# Main_ATMEGA328P.net
KiCad netlist of a schematic drawn in EAGLE
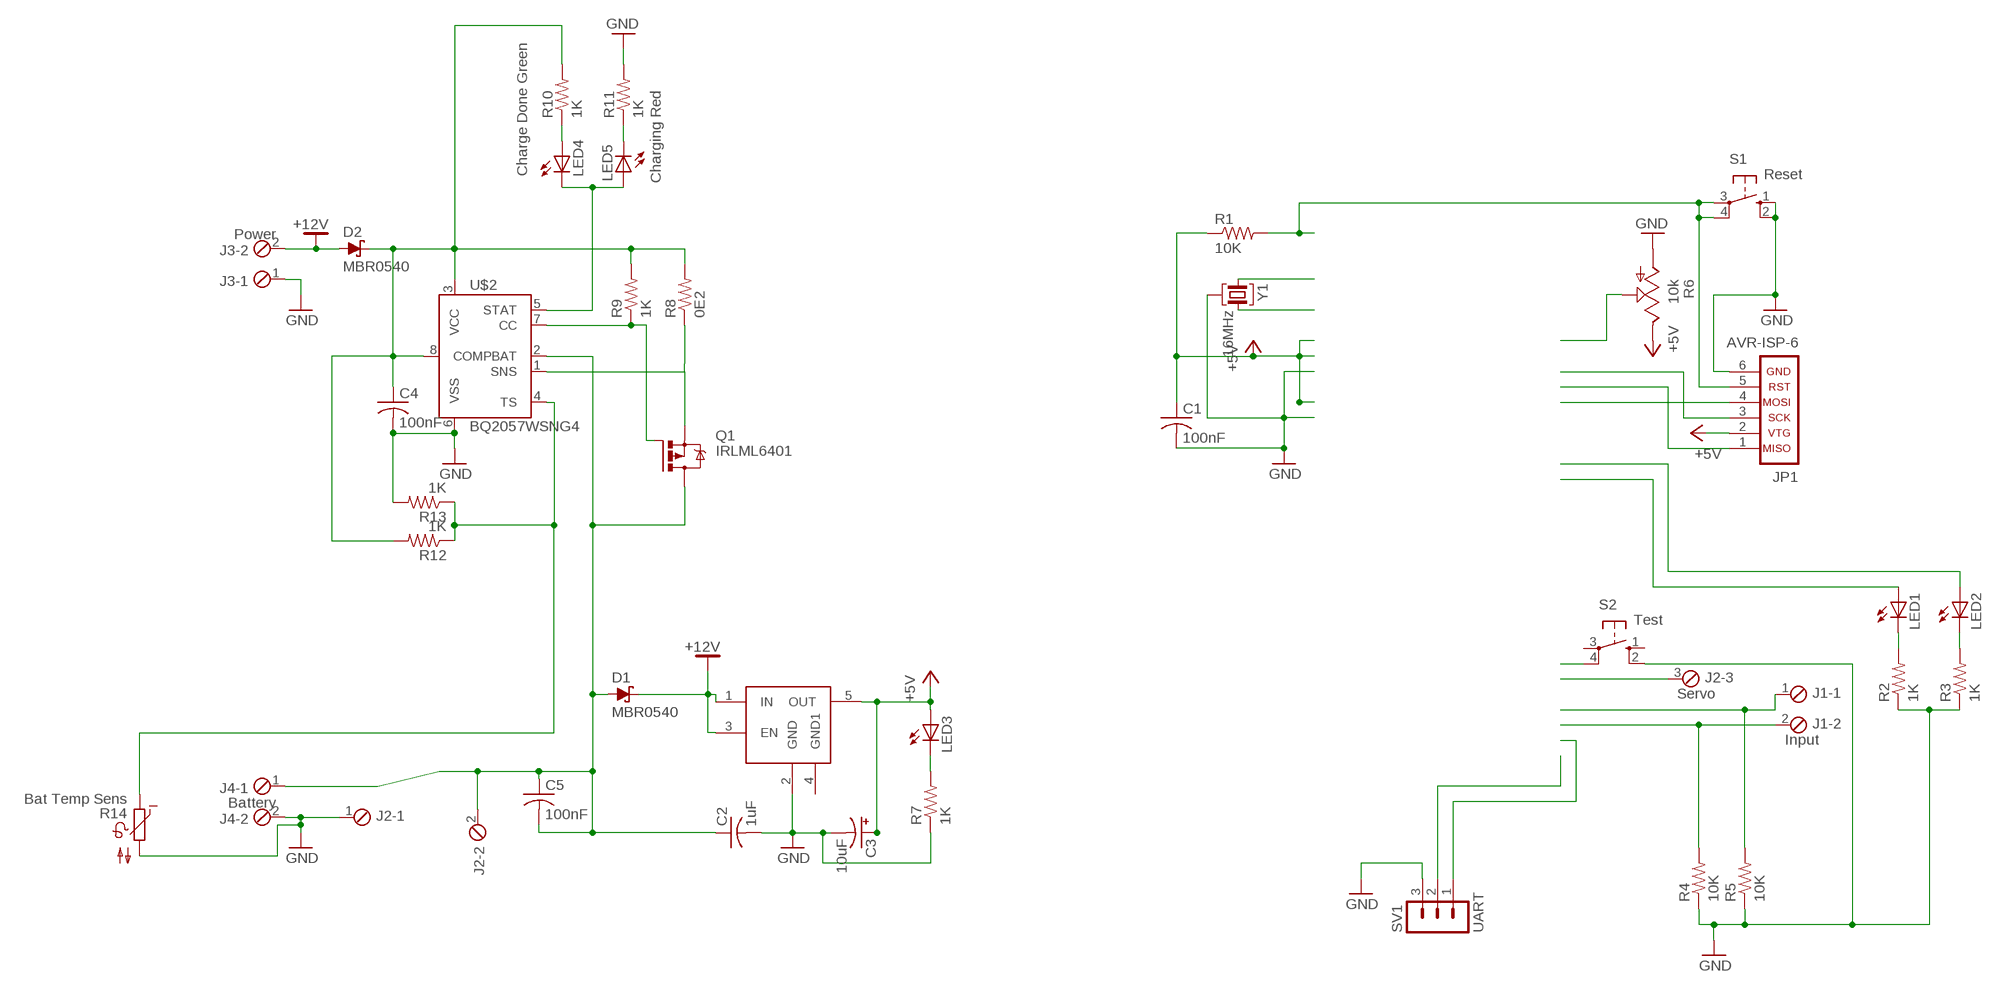
[diagram p0: schematic, sheet 1]

(export (version "E")
  (design (tool "Eeschema 10.0.6"))
  (components
    (comp (ref "C1")
      (value "100nF")
      (footprint "eagle-import:C0805K")
      (libsource (lib "eagle-import") (part "C-USC0805K"))
    )
    (comp (ref "C2")
      (value "1uF")
      (footprint "eagle-import:C0805K")
      (libsource (lib "eagle-import") (part "C-USC0805K"))
    )
    (comp (ref "C3")
      (value "10uF")
      (footprint "eagle-import:E2,5-7")
      (libsource (lib "eagle-import") (part "CPOL-USE2.5-7"))
    )
    (comp (ref "C4")
      (value "100nF")
      (footprint "eagle-import:C0805K")
      (libsource (lib "eagle-import") (part "C-USC0805K"))
    )
    (comp (ref "C5")
      (value "100nF")
      (footprint "eagle-import:C0805K")
      (libsource (lib "eagle-import") (part "C-USC0805K"))
    )
    (comp (ref "D1")
      (value "MBR0540")
      (footprint "eagle-import:SOD123")
      (libsource (lib "eagle-import") (part "MBR0540"))
    )
    (comp (ref "D2")
      (value "MBR0540")
      (footprint "eagle-import:SOD123")
      (libsource (lib "eagle-import") (part "MBR0540"))
    )
    (comp (ref "J1")
      (value "Input")
      (footprint "eagle-import:796689-2")
      (libsource (lib "eagle-import") (part "796689-2"))
    )
    (comp (ref "J2")
      (value "Servo")
      (footprint "eagle-import:796689-3")
      (libsource (lib "eagle-import") (part "796689-3"))
    )
    (comp (ref "J3")
      (value "Power")
      (footprint "eagle-import:796689-2")
      (libsource (lib "eagle-import") (part "796689-2"))
    )
    (comp (ref "J4")
      (value "Battery")
      (footprint "eagle-import:796689-2")
      (libsource (lib "eagle-import") (part "796689-2"))
    )
    (comp (ref "JP1")
      (value "AVR-ISP-6")
      (footprint "eagle-import:AVR-ISP-6")
      (libsource (lib "eagle-import") (part "AVR-ISP-6"))
    )
    (comp (ref "LED1")
      (value "LEDCHIPLED_0805")
      (footprint "eagle-import:CHIPLED_0805")
      (libsource (lib "eagle-import") (part "LEDCHIPLED_0805"))
    )
    (comp (ref "LED2")
      (value "LEDCHIPLED_0805")
      (footprint "eagle-import:CHIPLED_0805")
      (libsource (lib "eagle-import") (part "LEDCHIPLED_0805"))
    )
    (comp (ref "LED3")
      (value "LEDCHIPLED_0805")
      (footprint "eagle-import:CHIPLED_0805")
      (libsource (lib "eagle-import") (part "LEDCHIPLED_0805"))
    )
    (comp (ref "LED4")
      (value "Charge Done Green")
      (footprint "eagle-import:CHIPLED_0805")
      (libsource (lib "eagle-import") (part "LEDCHIPLED_0805"))
    )
    (comp (ref "LED5")
      (value "Charging Red")
      (footprint "eagle-import:CHIPLED_0805")
      (libsource (lib "eagle-import") (part "LEDCHIPLED_0805"))
    )
    (comp (ref "Q1")
      (value "IRLML6401")
      (footprint "eagle-import:MICRO3")
      (libsource (lib "eagle-import") (part "IRLML5203"))
    )
    (comp (ref "R1")
      (value "10K")
      (footprint "eagle-import:R0805")
      (libsource (lib "eagle-import") (part "R-US_R0805"))
    )
    (comp (ref "R2")
      (value "1K")
      (footprint "eagle-import:R0805")
      (libsource (lib "eagle-import") (part "R-US_R0805"))
    )
    (comp (ref "R3")
      (value "1K")
      (footprint "eagle-import:R0805")
      (libsource (lib "eagle-import") (part "R-US_R0805"))
    )
    (comp (ref "R4")
      (value "10K")
      (footprint "eagle-import:R0805")
      (libsource (lib "eagle-import") (part "R-US_R0805"))
    )
    (comp (ref "R5")
      (value "10K")
      (footprint "eagle-import:R0805")
      (libsource (lib "eagle-import") (part "R-US_R0805"))
    )
    (comp (ref "R6")
      (value "10k")
      (footprint "eagle-import:PT-10")
      (libsource (lib "eagle-import") (part "TRIM_US-PT-10"))
    )
    (comp (ref "R7")
      (value "1K")
      (footprint "eagle-import:R0805")
      (libsource (lib "eagle-import") (part "R-US_R0805"))
    )
    (comp (ref "R8")
      (value "0E2")
      (footprint "eagle-import:M1206")
      (libsource (lib "eagle-import") (part "R-US_M1206"))
    )
    (comp (ref "R9")
      (value "1K")
      (footprint "eagle-import:R0805")
      (libsource (lib "eagle-import") (part "R-US_R0805"))
    )
    (comp (ref "R10")
      (value "1K")
      (footprint "eagle-import:R0805")
      (libsource (lib "eagle-import") (part "R-US_R0805"))
    )
    (comp (ref "R11")
      (value "1K")
      (footprint "eagle-import:R0805")
      (libsource (lib "eagle-import") (part "R-US_R0805"))
    )
    (comp (ref "R12")
      (value "1K")
      (footprint "eagle-import:R0805")
      (libsource (lib "eagle-import") (part "R-US_R0805"))
    )
    (comp (ref "R13")
      (value "1K")
      (footprint "eagle-import:R0805")
      (libsource (lib "eagle-import") (part "R-US_R0805"))
    )
    (comp (ref "R14")
      (value "Bat Temp Sens")
      (footprint "eagle-import:P640")
      (libsource (lib "eagle-import") (part "NTC640"))
    )
    (comp (ref "S1")
      (value "Reset")
      (footprint "eagle-import:B3F-10XX")
      (fields (field (name "MPN") "B3F-1000"))
      (libsource (lib "eagle-import") (part "10-XX"))
    )
    (comp (ref "S2")
      (value "Test")
      (footprint "eagle-import:B3F-10XX")
      (fields (field (name "MPN") "B3F-1000"))
      (libsource (lib "eagle-import") (part "10-XX"))
    )
    (comp (ref "SV1")
      (value "UART")
      (footprint "eagle-import:MA03-1")
      (libsource (lib "eagle-import") (part "MA03-1"))
    )
    (comp (ref "U$1")
      (value "LP2981-50")
      (footprint "eagle-import:DBV-R-PDSO-G5")
      (libsource (lib "eagle-import") (part "TPS783XX"))
    )
    (comp (ref "U$2")
      (value "BQ2057WSNG4")
      (footprint "eagle-import:D_R-PDSO-G8")
      (libsource (lib "eagle-import") (part "BQ2057WSNG4"))
    )
    (comp (ref "Y1")
      (value "16MHz")
      (footprint "eagle-import:5X10-3")
      (libsource (lib "eagle-import") (part "ZTT5X10"))
    )
  )
  (nets
    (net (code "1") (name "+5V") (class "Default")
      (node (ref "C1") (pin "1") (pinfunction "1_1") (pintype "passive"))
      (node (ref "C3") (pin "+") (pinfunction "+_+") (pintype "passive"))
      (node (ref "JP1") (pin "2") (pinfunction "2_2") (pintype "passive"))
      (node (ref "LED3") (pin "A") (pinfunction "A_A") (pintype "passive"))
      (node (ref "R1") (pin "1") (pinfunction "1_1") (pintype "passive"))
      (node (ref "R6") (pin "E") (pinfunction "E_E") (pintype "passive"))
      (node (ref "U$1") (pin "5") (pinfunction "OUT_5") (pintype "bidirectional"))
    )
    (net (code "2") (name "+12V") (class "Default")
      (node (ref "D1") (pin "C") (pinfunction "C_C") (pintype "passive"))
      (node (ref "D2") (pin "A") (pinfunction "A_A") (pintype "passive"))
      (node (ref "J3") (pin "2") (pinfunction "1_2") (pintype "passive"))
      (node (ref "U$1") (pin "1") (pinfunction "IN_1") (pintype "bidirectional"))
      (node (ref "U$1") (pin "3") (pinfunction "EN_3") (pintype "bidirectional"))
    )
    (net (code "3") (name "GND") (class "Default")
      (node (ref "C1") (pin "2") (pinfunction "2_2") (pintype "passive"))
      (node (ref "C2") (pin "2") (pinfunction "2_2") (pintype "passive"))
      (node (ref "C3") (pin "-") (pinfunction "-_-") (pintype "passive"))
      (node (ref "C4") (pin "2") (pinfunction "2_2") (pintype "passive"))
      (node (ref "J2") (pin "1") (pinfunction "1_1") (pintype "passive"))
      (node (ref "J3") (pin "1") (pinfunction "1_1") (pintype "passive"))
      (node (ref "J4") (pin "2") (pinfunction "1_2") (pintype "passive"))
      (node (ref "JP1") (pin "6") (pinfunction "6_6") (pintype "passive"))
      (node (ref "R11") (pin "2") (pinfunction "2_2") (pintype "passive"))
      (node (ref "R13") (pin "2") (pinfunction "2_2") (pintype "passive"))
      (node (ref "R14") (pin "2") (pinfunction "2_2") (pintype "passive"))
      (node (ref "R2") (pin "1") (pinfunction "1_1") (pintype "passive"))
      (node (ref "R3") (pin "1") (pinfunction "1_1") (pintype "passive"))
      (node (ref "R4") (pin "1") (pinfunction "1_1") (pintype "passive"))
      (node (ref "R5") (pin "1") (pinfunction "1_1") (pintype "passive"))
      (node (ref "R6") (pin "A") (pinfunction "A_A") (pintype "passive"))
      (node (ref "R7") (pin "1") (pinfunction "1_1") (pintype "passive"))
      (node (ref "S1") (pin "1") (pinfunction "S_1") (pintype "passive"))
      (node (ref "S1") (pin "2") (pinfunction "S1_2") (pintype "passive"))
      (node (ref "S2") (pin "2") (pinfunction "S1_2") (pintype "passive"))
      (node (ref "SV1") (pin "3") (pinfunction "3_3") (pintype "passive"))
      (node (ref "U$1") (pin "2") (pinfunction "GND_2") (pintype "bidirectional"))
      (node (ref "U$2") (pin "6") (pinfunction "VSS_6") (pintype "power_in"))
      (node (ref "Y1") (pin "2") (pinfunction "2_2") (pintype "passive"))
    )
    (net (code "4") (name "Net-(J1-Pad1)") (class "Default")
      (node (ref "J1") (pin "1") (pinfunction "1_1") (pintype "passive"))
      (node (ref "R5") (pin "2") (pinfunction "2_2") (pintype "passive"))
    )
    (net (code "5") (name "Net-(J1B-1)") (class "Default")
      (node (ref "J1") (pin "2") (pinfunction "1_2") (pintype "passive"))
      (node (ref "R4") (pin "2") (pinfunction "2_2") (pintype "passive"))
    )
    (net (code "6") (name "Net-(J2B-1)") (class "Default")
      (node (ref "C2") (pin "1") (pinfunction "1_1") (pintype "passive"))
      (node (ref "C5") (pin "1") (pinfunction "1_1") (pintype "passive"))
      (node (ref "C5") (pin "2") (pinfunction "2_2") (pintype "passive"))
      (node (ref "D1") (pin "A") (pinfunction "A_A") (pintype "passive"))
      (node (ref "J2") (pin "2") (pinfunction "1_2") (pintype "passive"))
      (node (ref "J4") (pin "1") (pinfunction "1_1") (pintype "passive"))
      (node (ref "Q1") (pin "3") (pinfunction "D_3") (pintype "passive"))
      (node (ref "U$2") (pin "2") (pinfunction "BAT_2") (pintype "input"))
    )
    (net (code "7") (name "Net-(LED1-PadC)") (class "Default")
      (node (ref "LED1") (pin "C") (pinfunction "C_C") (pintype "passive"))
      (node (ref "R2") (pin "2") (pinfunction "2_2") (pintype "passive"))
    )
    (net (code "8") (name "Net-(LED2-PadC)") (class "Default")
      (node (ref "LED2") (pin "C") (pinfunction "C_C") (pintype "passive"))
      (node (ref "R3") (pin "2") (pinfunction "2_2") (pintype "passive"))
    )
    (net (code "9") (name "Net-(LED3-PadC)") (class "Default")
      (node (ref "LED3") (pin "C") (pinfunction "C_C") (pintype "passive"))
      (node (ref "R7") (pin "2") (pinfunction "2_2") (pintype "passive"))
    )
    (net (code "10") (name "Net-(LED4-PadA)") (class "Default")
      (node (ref "LED4") (pin "A") (pinfunction "A_A") (pintype "passive"))
      (node (ref "R10") (pin "1") (pinfunction "1_1") (pintype "passive"))
    )
    (net (code "11") (name "Net-(LED5-PadC)") (class "Default")
      (node (ref "LED5") (pin "C") (pinfunction "C_C") (pintype "passive"))
      (node (ref "R11") (pin "1") (pinfunction "1_1") (pintype "passive"))
    )
    (net (code "12") (name "Net-(Q1-G)") (class "Default")
      (node (ref "Q1") (pin "1") (pinfunction "G_1") (pintype "passive"))
      (node (ref "R9") (pin "1") (pinfunction "1_1") (pintype "passive"))
      (node (ref "U$2") (pin "7") (pinfunction "CC_7") (pintype "output"))
    )
    (net (code "13") (name "Net-(Q1-S)") (class "Default")
      (node (ref "Q1") (pin "2") (pinfunction "S_2") (pintype "passive"))
      (node (ref "R8") (pin "1") (pinfunction "1_1") (pintype "passive"))
      (node (ref "U$2") (pin "1") (pinfunction "SNS_1") (pintype "input"))
    )
    (net (code "14") (name "Net-(S1-P)") (class "Default")
      (node (ref "JP1") (pin "5") (pinfunction "5_5") (pintype "passive"))
      (node (ref "R1") (pin "2") (pinfunction "2_2") (pintype "passive"))
      (node (ref "S1") (pin "3") (pinfunction "P_3") (pintype "passive"))
      (node (ref "S1") (pin "4") (pinfunction "P1_4") (pintype "passive"))
    )
    (net (code "15") (name "Net-(U$2-COMP)") (class "Default")
      (node (ref "C4") (pin "1") (pinfunction "1_1") (pintype "passive"))
      (node (ref "D2") (pin "C") (pinfunction "C_C") (pintype "passive"))
      (node (ref "R10") (pin "2") (pinfunction "2_2") (pintype "passive"))
      (node (ref "R12") (pin "2") (pinfunction "2_2") (pintype "passive"))
      (node (ref "R8") (pin "2") (pinfunction "2_2") (pintype "passive"))
      (node (ref "R9") (pin "2") (pinfunction "2_2") (pintype "passive"))
      (node (ref "U$2") (pin "3") (pinfunction "VCC_3") (pintype "input"))
      (node (ref "U$2") (pin "8") (pinfunction "COMP_8") (pintype "input"))
    )
    (net (code "16") (name "Net-(U$2-STAT)") (class "Default")
      (node (ref "LED4") (pin "C") (pinfunction "C_C") (pintype "passive"))
      (node (ref "LED5") (pin "A") (pinfunction "A_A") (pintype "passive"))
      (node (ref "U$2") (pin "5") (pinfunction "STAT_5") (pintype "output"))
    )
    (net (code "17") (name "Net-(U$2-TS)") (class "Default")
      (node (ref "R12") (pin "1") (pinfunction "1_1") (pintype "passive"))
      (node (ref "R13") (pin "1") (pinfunction "1_1") (pintype "passive"))
      (node (ref "R14") (pin "1") (pinfunction "1_1") (pintype "passive"))
      (node (ref "U$2") (pin "4") (pinfunction "TS_4") (pintype "input"))
    )
    (net (code "18") (name "unconnected-(J2C-1-Pad3)") (class "Default")
      (node (ref "J2") (pin "3") (pinfunction "1_3") (pintype "passive"))
    )
    (net (code "19") (name "unconnected-(JP1-Pad1)") (class "Default")
      (node (ref "JP1") (pin "1") (pinfunction "1_1") (pintype "passive"))
    )
    (net (code "20") (name "unconnected-(JP1-Pad3)") (class "Default")
      (node (ref "JP1") (pin "3") (pinfunction "3_3") (pintype "passive"))
    )
    (net (code "21") (name "unconnected-(JP1-Pad4)") (class "Default")
      (node (ref "JP1") (pin "4") (pinfunction "4_4") (pintype "passive"))
    )
    (net (code "22") (name "unconnected-(LED1-PadA)") (class "Default")
      (node (ref "LED1") (pin "A") (pinfunction "A_A") (pintype "passive"))
    )
    (net (code "23") (name "unconnected-(LED2-PadA)") (class "Default")
      (node (ref "LED2") (pin "A") (pinfunction "A_A") (pintype "passive"))
    )
    (net (code "24") (name "unconnected-(R6-PadS)") (class "Default")
      (node (ref "R6") (pin "S") (pinfunction "S_S") (pintype "passive"))
    )
    (net (code "25") (name "unconnected-(S2-P-Pad3)") (class "Default")
      (node (ref "S2") (pin "3") (pinfunction "P_3") (pintype "passive"))
    )
    (net (code "26") (name "unconnected-(S2-P1-Pad4)") (class "Default")
      (node (ref "S2") (pin "4") (pinfunction "P1_4") (pintype "passive"))
    )
    (net (code "27") (name "unconnected-(S2-S-Pad1)") (class "Default")
      (node (ref "S2") (pin "1") (pinfunction "S_1") (pintype "passive"))
    )
    (net (code "28") (name "unconnected-(SV1-Pad1)") (class "Default")
      (node (ref "SV1") (pin "1") (pinfunction "1_1") (pintype "passive"))
    )
    (net (code "29") (name "unconnected-(SV1-Pad2)") (class "Default")
      (node (ref "SV1") (pin "2") (pinfunction "2_2") (pintype "passive"))
    )
    (net (code "30") (name "unconnected-(U$1-GND1-Pad4)") (class "Default")
      (node (ref "U$1") (pin "4") (pinfunction "GND1_4") (pintype "bidirectional"))
    )
    (net (code "31") (name "unconnected-(Y1-Pad1)") (class "Default")
      (node (ref "Y1") (pin "1") (pinfunction "1_1") (pintype "passive"))
    )
    (net (code "32") (name "unconnected-(Y1-Pad3)") (class "Default")
      (node (ref "Y1") (pin "3") (pinfunction "3_3") (pintype "passive"))
    )
  )
)
